# motor_frontplane.net
KiCad netlist of a schematic drawn in EAGLE
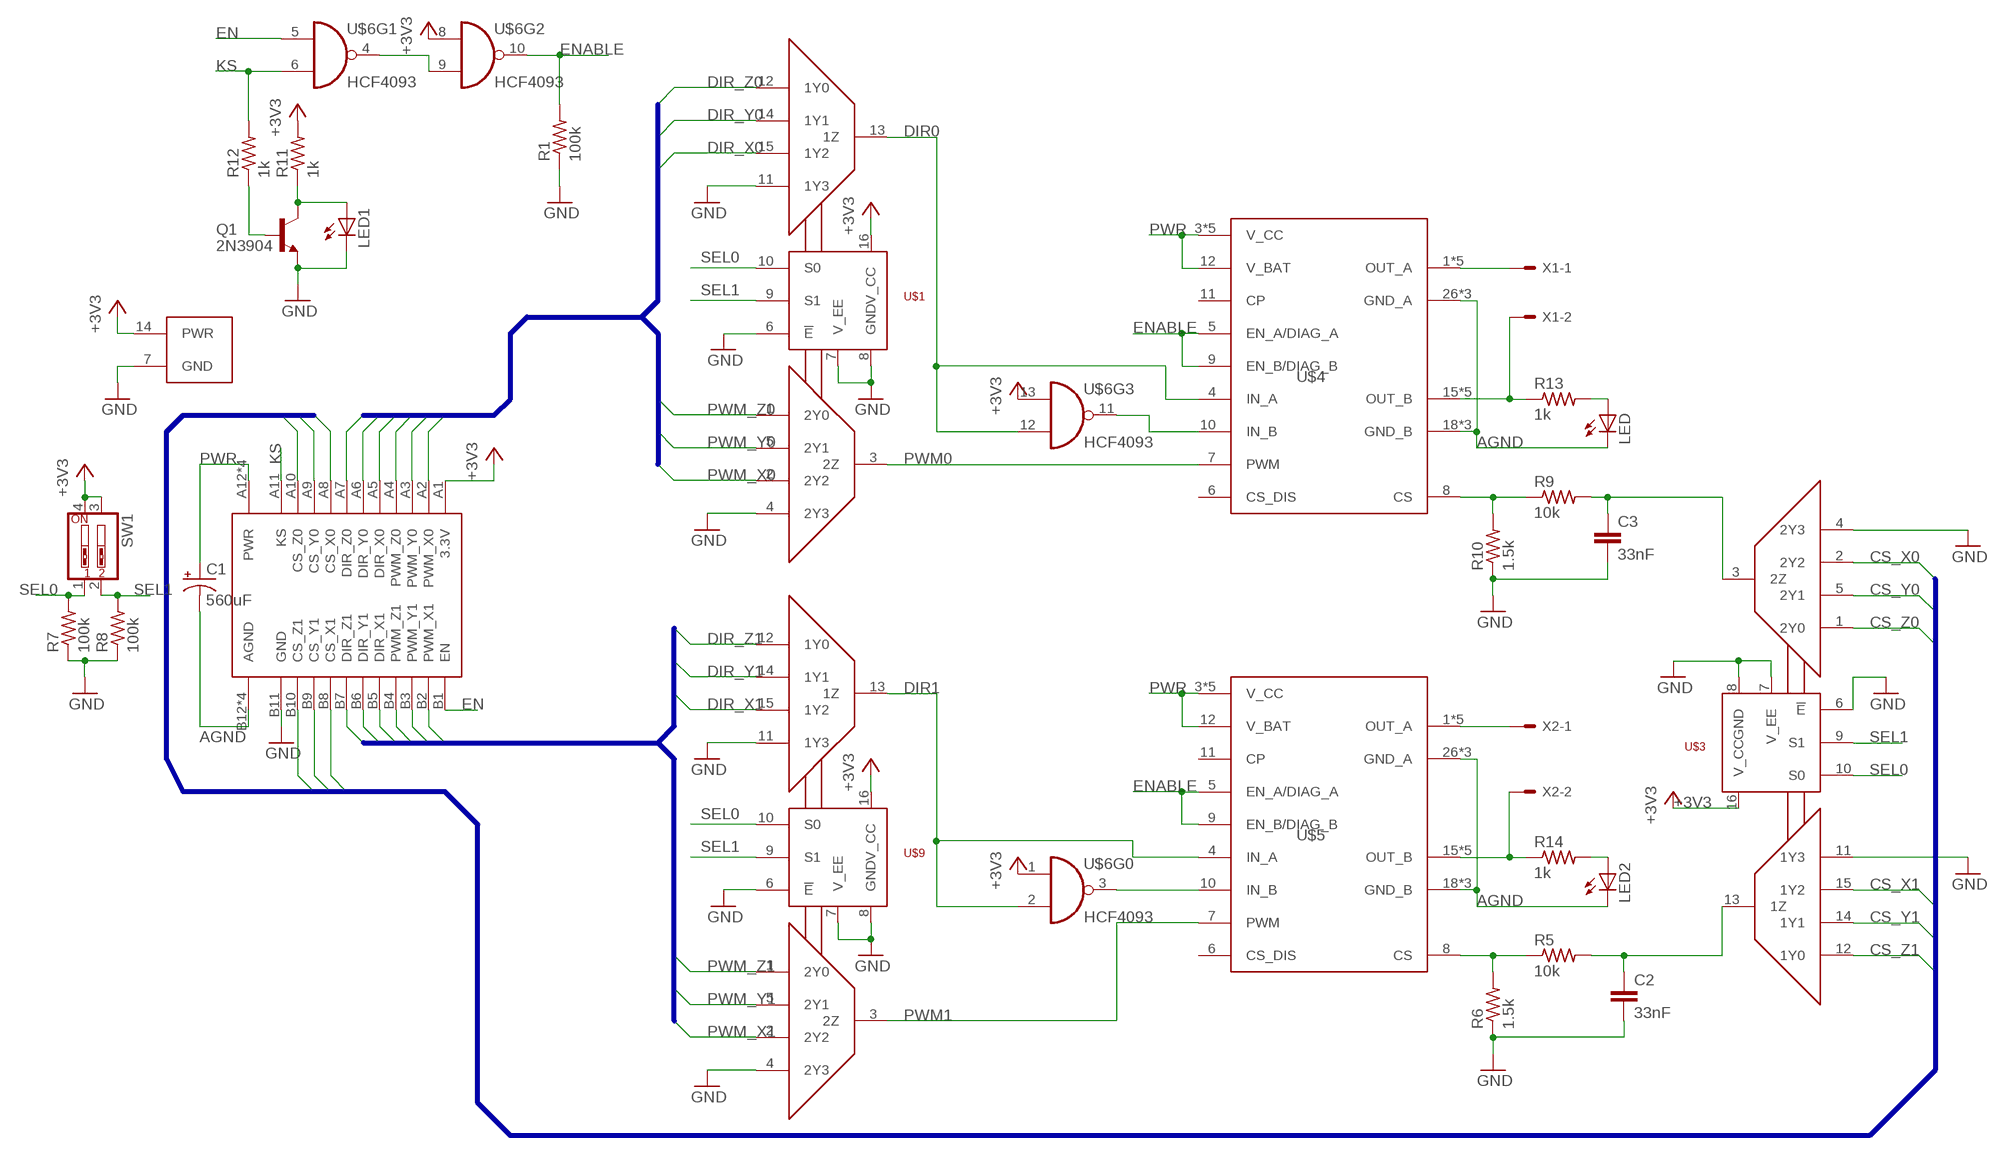
[diagram p0: schematic, sheet 1]

(export (version "E")
  (design (tool "Eeschema 10.0.6"))
  (components
    (comp (ref "C1")
      (value "560uF")
      (footprint "eagle-import:E3,5-10")
      (libsource (lib "eagle-import") (part "CPOL-USE3.5-10"))
    )
    (comp (ref "C2")
      (value "33nF")
      (footprint "eagle-import:C2.5-2")
      (libsource (lib "eagle-import") (part "C2.5/2"))
    )
    (comp (ref "C3")
      (value "33nF")
      (footprint "eagle-import:C2.5-2")
      (libsource (lib "eagle-import") (part "C2.5/2"))
    )
    (comp (ref "LED")
      (value "LED5MM")
      (footprint "eagle-import:LED5MM")
      (libsource (lib "eagle-import") (part "LED5MM"))
    )
    (comp (ref "LED1")
      (value "LED5MM")
      (footprint "eagle-import:LED5MM")
      (libsource (lib "eagle-import") (part "LED5MM"))
    )
    (comp (ref "LED2")
      (value "LED5MM")
      (footprint "eagle-import:LED5MM")
      (libsource (lib "eagle-import") (part "LED5MM"))
    )
    (comp (ref "Q1")
      (value "2N3904")
      (footprint "eagle-import:TO92")
      (libsource (lib "eagle-import") (part "2N3904"))
    )
    (comp (ref "R1")
      (value "100k")
      (footprint "eagle-import:R0805")
      (libsource (lib "eagle-import") (part "R-US_R0805"))
    )
    (comp (ref "R5")
      (value "10k")
      (footprint "eagle-import:R0805")
      (libsource (lib "eagle-import") (part "R-US_R0805"))
    )
    (comp (ref "R6")
      (value "1.5k")
      (footprint "eagle-import:R0805")
      (libsource (lib "eagle-import") (part "R-US_R0805"))
    )
    (comp (ref "R7")
      (value "100k")
      (footprint "eagle-import:R0805")
      (libsource (lib "eagle-import") (part "R-US_R0805"))
    )
    (comp (ref "R8")
      (value "100k")
      (footprint "eagle-import:R0805")
      (libsource (lib "eagle-import") (part "R-US_R0805"))
    )
    (comp (ref "R9")
      (value "10k")
      (footprint "eagle-import:R0805")
      (libsource (lib "eagle-import") (part "R-US_R0805"))
    )
    (comp (ref "R10")
      (value "1.5k")
      (footprint "eagle-import:R0805")
      (libsource (lib "eagle-import") (part "R-US_R0805"))
    )
    (comp (ref "R11")
      (value "1k")
      (footprint "eagle-import:R0805")
      (libsource (lib "eagle-import") (part "R-US_R0805"))
    )
    (comp (ref "R12")
      (value "1k")
      (footprint "eagle-import:R0805")
      (libsource (lib "eagle-import") (part "R-US_R0805"))
    )
    (comp (ref "R13")
      (value "1k")
      (footprint "eagle-import:R0805")
      (libsource (lib "eagle-import") (part "R-US_R0805"))
    )
    (comp (ref "R14")
      (value "1k")
      (footprint "eagle-import:R0805")
      (libsource (lib "eagle-import") (part "R-US_R0805"))
    )
    (comp (ref "SW1")
      (value "SW_DIP-2")
      (footprint "eagle-import:EDG-02")
      (libsource (lib "eagle-import") (part "SW_DIP-2"))
    )
    (comp (ref "U$1")
      (value "74HC4052-Q100")
      (footprint "eagle-import:SO16")
      (libsource (lib "eagle-import") (part "74HC4052-Q100"))
    )
    (comp (ref "U$2")
      (value "MOTOR_BOARD_CONN")
      (footprint "eagle-import:CARD_30PIN_8PWR")
      (libsource (lib "eagle-import") (part "MOTOR_BOARD_CONN"))
    )
    (comp (ref "U$3")
      (value "74HC4052-Q100")
      (footprint "eagle-import:SO16")
      (libsource (lib "eagle-import") (part "74HC4052-Q100"))
    )
    (comp (ref "U$4")
      (value "VNH5019A-E")
      (footprint "eagle-import:MULTIPOWERSO-30")
      (libsource (lib "eagle-import") (part "VNH5019A-E"))
    )
    (comp (ref "U$5")
      (value "VNH5019A-E")
      (footprint "eagle-import:MULTIPOWERSO-30")
      (libsource (lib "eagle-import") (part "VNH5019A-E"))
    )
    (comp (ref "U$6")
      (value "HCF4093")
      (footprint "eagle-import:SO14")
      (libsource (lib "eagle-import") (part "HCF4093"))
    )
    (comp (ref "U$9")
      (value "74HC4052-Q100")
      (footprint "eagle-import:SO16")
      (libsource (lib "eagle-import") (part "74HC4052-Q100"))
    )
    (comp (ref "X1")
      (value "KK-156-2")
      (footprint "eagle-import:KK-156-2")
      (libsource (lib "eagle-import") (part "KK-156-2"))
    )
    (comp (ref "X2")
      (value "KK-156-2")
      (footprint "eagle-import:KK-156-2")
      (libsource (lib "eagle-import") (part "KK-156-2"))
    )
  )
  (nets
    (net (code "1") (name "+3V3") (class "Default")
      (node (ref "R11") (pin "2") (pinfunction "2_2") (pintype "passive"))
      (node (ref "SW1") (pin "3") (pinfunction "3_3") (pintype "passive"))
      (node (ref "SW1") (pin "4") (pinfunction "4_4") (pintype "passive"))
      (node (ref "U$1") (pin "16") (pinfunction "V_CC_16") (pintype "bidirectional"))
      (node (ref "U$2") (pin "A1") (pinfunction "3.3V_A1") (pintype "bidirectional"))
      (node (ref "U$3") (pin "16") (pinfunction "V_CC_16") (pintype "bidirectional"))
      (node (ref "U$6") (pin "1") (pinfunction "I0_1") (pintype "input"))
      (node (ref "U$6") (pin "13") (pinfunction "I0_13") (pintype "input"))
      (node (ref "U$6") (pin "14") (pinfunction "PWR_14") (pintype "bidirectional"))
      (node (ref "U$6") (pin "8") (pinfunction "I0_8") (pintype "input"))
      (node (ref "U$9") (pin "16") (pinfunction "V_CC_16") (pintype "bidirectional"))
    )
    (net (code "2") (name "/AGND") (class "Default")
      (node (ref "C1") (pin "-") (pinfunction "-_-") (pintype "passive"))
      (node (ref "LED") (pin "K") (pinfunction "C_K") (pintype "passive"))
      (node (ref "LED2") (pin "K") (pinfunction "C_K") (pintype "passive"))
      (node (ref "U$2") (pin "B12") (pinfunction "AGND_B12") (pintype "bidirectional"))
      (node (ref "U$2") (pin "B13") (pinfunction "AGND_B13") (pintype "bidirectional"))
      (node (ref "U$2") (pin "B14") (pinfunction "AGND_B14") (pintype "bidirectional"))
      (node (ref "U$2") (pin "B15") (pinfunction "AGND_B15") (pintype "bidirectional"))
      (node (ref "U$4") (pin "18") (pinfunction "GND_B_18") (pintype "bidirectional"))
      (node (ref "U$4") (pin "19") (pinfunction "GND_B_19") (pintype "bidirectional"))
      (node (ref "U$4") (pin "20") (pinfunction "GND_B_20") (pintype "bidirectional"))
      (node (ref "U$4") (pin "26") (pinfunction "GND_A_26") (pintype "bidirectional"))
      (node (ref "U$4") (pin "27") (pinfunction "GND_A_27") (pintype "bidirectional"))
      (node (ref "U$4") (pin "28") (pinfunction "GND_A_28") (pintype "bidirectional"))
      (node (ref "U$5") (pin "18") (pinfunction "GND_B_18") (pintype "bidirectional"))
      (node (ref "U$5") (pin "19") (pinfunction "GND_B_19") (pintype "bidirectional"))
      (node (ref "U$5") (pin "20") (pinfunction "GND_B_20") (pintype "bidirectional"))
      (node (ref "U$5") (pin "26") (pinfunction "GND_A_26") (pintype "bidirectional"))
      (node (ref "U$5") (pin "27") (pinfunction "GND_A_27") (pintype "bidirectional"))
      (node (ref "U$5") (pin "28") (pinfunction "GND_A_28") (pintype "bidirectional"))
    )
    (net (code "3") (name "/CS_X0") (class "Default")
      (node (ref "U$2") (pin "A8") (pinfunction "CS_X0_A8") (pintype "bidirectional"))
      (node (ref "U$3") (pin "2") (pinfunction "2Y2_2") (pintype "bidirectional"))
    )
    (net (code "4") (name "/CS_X1") (class "Default")
      (node (ref "U$2") (pin "B8") (pinfunction "CS_X1_B8") (pintype "bidirectional"))
      (node (ref "U$3") (pin "15") (pinfunction "1Y2_15") (pintype "bidirectional"))
    )
    (net (code "5") (name "/CS_Y0") (class "Default")
      (node (ref "U$2") (pin "A9") (pinfunction "CS_Y0_A9") (pintype "bidirectional"))
      (node (ref "U$3") (pin "5") (pinfunction "2Y1_5") (pintype "bidirectional"))
    )
    (net (code "6") (name "/CS_Y1") (class "Default")
      (node (ref "U$2") (pin "B9") (pinfunction "CS_Y1_B9") (pintype "bidirectional"))
      (node (ref "U$3") (pin "14") (pinfunction "1Y1_14") (pintype "bidirectional"))
    )
    (net (code "7") (name "/CS_Z0") (class "Default")
      (node (ref "U$2") (pin "A10") (pinfunction "CS_Z0_A10") (pintype "bidirectional"))
      (node (ref "U$3") (pin "1") (pinfunction "2Y0_1") (pintype "bidirectional"))
    )
    (net (code "8") (name "/CS_Z1") (class "Default")
      (node (ref "U$2") (pin "B10") (pinfunction "CS_Z1_B10") (pintype "bidirectional"))
      (node (ref "U$3") (pin "12") (pinfunction "1Y0_12") (pintype "bidirectional"))
    )
    (net (code "9") (name "/DIR0") (class "Default")
      (node (ref "U$1") (pin "13") (pinfunction "1Z_13") (pintype "bidirectional"))
      (node (ref "U$4") (pin "4") (pinfunction "IN_A_4") (pintype "bidirectional"))
      (node (ref "U$6") (pin "12") (pinfunction "I1_12") (pintype "input"))
    )
    (net (code "10") (name "/DIR1") (class "Default")
      (node (ref "U$5") (pin "4") (pinfunction "IN_A_4") (pintype "bidirectional"))
      (node (ref "U$6") (pin "2") (pinfunction "I1_2") (pintype "input"))
      (node (ref "U$9") (pin "13") (pinfunction "1Z_13") (pintype "bidirectional"))
    )
    (net (code "11") (name "/DIR_X0") (class "Default")
      (node (ref "U$1") (pin "15") (pinfunction "1Y2_15") (pintype "bidirectional"))
      (node (ref "U$2") (pin "A5") (pinfunction "DIR_X0_A5") (pintype "bidirectional"))
    )
    (net (code "12") (name "/DIR_X1") (class "Default")
      (node (ref "U$2") (pin "B5") (pinfunction "DIR_X1_B5") (pintype "bidirectional"))
      (node (ref "U$9") (pin "15") (pinfunction "1Y2_15") (pintype "bidirectional"))
    )
    (net (code "13") (name "/DIR_Y0") (class "Default")
      (node (ref "U$1") (pin "14") (pinfunction "1Y1_14") (pintype "bidirectional"))
      (node (ref "U$2") (pin "A6") (pinfunction "DIR_Y0_A6") (pintype "bidirectional"))
    )
    (net (code "14") (name "/DIR_Y1") (class "Default")
      (node (ref "U$2") (pin "B6") (pinfunction "DIR_Y1_B6") (pintype "bidirectional"))
      (node (ref "U$9") (pin "14") (pinfunction "1Y1_14") (pintype "bidirectional"))
    )
    (net (code "15") (name "/DIR_Z0") (class "Default")
      (node (ref "U$1") (pin "12") (pinfunction "1Y0_12") (pintype "bidirectional"))
      (node (ref "U$2") (pin "A7") (pinfunction "DIR_Z0_A7") (pintype "bidirectional"))
    )
    (net (code "16") (name "/DIR_Z1") (class "Default")
      (node (ref "U$2") (pin "B7") (pinfunction "DIR_Z1_B7") (pintype "bidirectional"))
      (node (ref "U$9") (pin "12") (pinfunction "1Y0_12") (pintype "bidirectional"))
    )
    (net (code "17") (name "/EN") (class "Default")
      (node (ref "U$2") (pin "B1") (pinfunction "EN_B1") (pintype "bidirectional"))
      (node (ref "U$6") (pin "5") (pinfunction "I0_5") (pintype "input"))
    )
    (net (code "18") (name "/ENABLE") (class "Default")
      (node (ref "R1") (pin "2") (pinfunction "2_2") (pintype "passive"))
      (node (ref "U$4") (pin "5") (pinfunction "EN_A/DIAG_A_5") (pintype "bidirectional"))
      (node (ref "U$4") (pin "9") (pinfunction "EN_B/DIAG_B_9") (pintype "bidirectional"))
      (node (ref "U$5") (pin "5") (pinfunction "EN_A/DIAG_A_5") (pintype "bidirectional"))
      (node (ref "U$5") (pin "9") (pinfunction "EN_B/DIAG_B_9") (pintype "bidirectional"))
      (node (ref "U$6") (pin "10") (pinfunction "O_10") (pintype "output"))
    )
    (net (code "19") (name "/KS") (class "Default")
      (node (ref "R12") (pin "2") (pinfunction "2_2") (pintype "passive"))
      (node (ref "U$2") (pin "A11") (pinfunction "KS_A11") (pintype "bidirectional"))
      (node (ref "U$6") (pin "6") (pinfunction "I1_6") (pintype "input"))
    )
    (net (code "20") (name "/PWM0") (class "Default")
      (node (ref "U$1") (pin "3") (pinfunction "2Z_3") (pintype "bidirectional"))
      (node (ref "U$4") (pin "7") (pinfunction "PWM_7") (pintype "bidirectional"))
    )
    (net (code "21") (name "/PWM1") (class "Default")
      (node (ref "U$5") (pin "7") (pinfunction "PWM_7") (pintype "bidirectional"))
      (node (ref "U$9") (pin "3") (pinfunction "2Z_3") (pintype "bidirectional"))
    )
    (net (code "22") (name "/PWM_X0") (class "Default")
      (node (ref "U$1") (pin "2") (pinfunction "2Y2_2") (pintype "bidirectional"))
      (node (ref "U$2") (pin "A2") (pinfunction "PWM_X0_A2") (pintype "bidirectional"))
    )
    (net (code "23") (name "/PWM_X1") (class "Default")
      (node (ref "U$2") (pin "B2") (pinfunction "PWM_X1_B2") (pintype "bidirectional"))
      (node (ref "U$9") (pin "2") (pinfunction "2Y2_2") (pintype "bidirectional"))
    )
    (net (code "24") (name "/PWM_Y0") (class "Default")
      (node (ref "U$1") (pin "5") (pinfunction "2Y1_5") (pintype "bidirectional"))
      (node (ref "U$2") (pin "A3") (pinfunction "PWM_Y0_A3") (pintype "bidirectional"))
    )
    (net (code "25") (name "/PWM_Y1") (class "Default")
      (node (ref "U$2") (pin "B3") (pinfunction "PWM_Y1_B3") (pintype "bidirectional"))
      (node (ref "U$9") (pin "5") (pinfunction "2Y1_5") (pintype "bidirectional"))
    )
    (net (code "26") (name "/PWM_Z0") (class "Default")
      (node (ref "U$1") (pin "1") (pinfunction "2Y0_1") (pintype "bidirectional"))
      (node (ref "U$2") (pin "A4") (pinfunction "PWM_Z0_A4") (pintype "bidirectional"))
    )
    (net (code "27") (name "/PWM_Z1") (class "Default")
      (node (ref "U$2") (pin "B4") (pinfunction "PWM_Z1_B4") (pintype "bidirectional"))
      (node (ref "U$9") (pin "1") (pinfunction "2Y0_1") (pintype "bidirectional"))
    )
    (net (code "28") (name "/PWR") (class "Default")
      (node (ref "C1") (pin "+") (pinfunction "+_+") (pintype "passive"))
      (node (ref "U$2") (pin "A12") (pinfunction "PWR_A12") (pintype "bidirectional"))
      (node (ref "U$2") (pin "A13") (pinfunction "PWR_A13") (pintype "bidirectional"))
      (node (ref "U$2") (pin "A14") (pinfunction "PWR_A14") (pintype "bidirectional"))
      (node (ref "U$2") (pin "A15") (pinfunction "PWR_A15") (pintype "bidirectional"))
      (node (ref "U$4") (pin "12") (pinfunction "V_BAT_12") (pintype "bidirectional"))
      (node (ref "U$4") (pin "13") (pinfunction "V_CC_13") (pintype "bidirectional"))
      (node (ref "U$4") (pin "23") (pinfunction "V_CC_23") (pintype "bidirectional"))
      (node (ref "U$4") (pin "3") (pinfunction "V_CC_3") (pintype "bidirectional"))
      (node (ref "U$4") (pin "VCC") (pinfunction "V_CC_VCC") (pintype "bidirectional"))
      (node (ref "U$4") (pin "VCC@1") (pinfunction "V_CC_VCC@1") (pintype "bidirectional"))
      (node (ref "U$5") (pin "12") (pinfunction "V_BAT_12") (pintype "bidirectional"))
      (node (ref "U$5") (pin "13") (pinfunction "V_CC_13") (pintype "bidirectional"))
      (node (ref "U$5") (pin "23") (pinfunction "V_CC_23") (pintype "bidirectional"))
      (node (ref "U$5") (pin "3") (pinfunction "V_CC_3") (pintype "bidirectional"))
      (node (ref "U$5") (pin "VCC") (pinfunction "V_CC_VCC") (pintype "bidirectional"))
      (node (ref "U$5") (pin "VCC@1") (pinfunction "V_CC_VCC@1") (pintype "bidirectional"))
    )
    (net (code "29") (name "/SEL0") (class "Default")
      (node (ref "R7") (pin "2") (pinfunction "2_2") (pintype "passive"))
      (node (ref "SW1") (pin "1") (pinfunction "1_1") (pintype "passive"))
      (node (ref "U$1") (pin "10") (pinfunction "S0_10") (pintype "bidirectional"))
      (node (ref "U$3") (pin "10") (pinfunction "S0_10") (pintype "bidirectional"))
      (node (ref "U$9") (pin "10") (pinfunction "S0_10") (pintype "bidirectional"))
    )
    (net (code "30") (name "/SEL1") (class "Default")
      (node (ref "R8") (pin "2") (pinfunction "2_2") (pintype "passive"))
      (node (ref "SW1") (pin "2") (pinfunction "2_2") (pintype "passive"))
      (node (ref "U$1") (pin "9") (pinfunction "S1_9") (pintype "bidirectional"))
      (node (ref "U$3") (pin "9") (pinfunction "S1_9") (pintype "bidirectional"))
      (node (ref "U$9") (pin "9") (pinfunction "S1_9") (pintype "bidirectional"))
    )
    (net (code "31") (name "GND") (class "Default")
      (node (ref "C2") (pin "2") (pinfunction "2_2") (pintype "passive"))
      (node (ref "C3") (pin "2") (pinfunction "2_2") (pintype "passive"))
      (node (ref "LED1") (pin "K") (pinfunction "C_K") (pintype "passive"))
      (node (ref "Q1") (pin "3") (pinfunction "E_3") (pintype "passive"))
      (node (ref "R1") (pin "1") (pinfunction "1_1") (pintype "passive"))
      (node (ref "R10") (pin "1") (pinfunction "1_1") (pintype "passive"))
      (node (ref "R6") (pin "1") (pinfunction "1_1") (pintype "passive"))
      (node (ref "R7") (pin "1") (pinfunction "1_1") (pintype "passive"))
      (node (ref "R8") (pin "1") (pinfunction "1_1") (pintype "passive"))
      (node (ref "U$1") (pin "11") (pinfunction "1Y3_11") (pintype "bidirectional"))
      (node (ref "U$1") (pin "4") (pinfunction "2Y3_4") (pintype "bidirectional"))
      (node (ref "U$1") (pin "6") (pinfunction "~{E}_6") (pintype "bidirectional"))
      (node (ref "U$1") (pin "7") (pinfunction "V_EE_7") (pintype "bidirectional"))
      (node (ref "U$1") (pin "8") (pinfunction "GND_8") (pintype "bidirectional"))
      (node (ref "U$2") (pin "B11") (pinfunction "GND_B11") (pintype "bidirectional"))
      (node (ref "U$3") (pin "11") (pinfunction "1Y3_11") (pintype "bidirectional"))
      (node (ref "U$3") (pin "4") (pinfunction "2Y3_4") (pintype "bidirectional"))
      (node (ref "U$3") (pin "6") (pinfunction "~{E}_6") (pintype "bidirectional"))
      (node (ref "U$3") (pin "7") (pinfunction "V_EE_7") (pintype "bidirectional"))
      (node (ref "U$3") (pin "8") (pinfunction "GND_8") (pintype "bidirectional"))
      (node (ref "U$6") (pin "7") (pinfunction "GND_7") (pintype "bidirectional"))
      (node (ref "U$9") (pin "11") (pinfunction "1Y3_11") (pintype "bidirectional"))
      (node (ref "U$9") (pin "4") (pinfunction "2Y3_4") (pintype "bidirectional"))
      (node (ref "U$9") (pin "6") (pinfunction "~{E}_6") (pintype "bidirectional"))
      (node (ref "U$9") (pin "7") (pinfunction "V_EE_7") (pintype "bidirectional"))
      (node (ref "U$9") (pin "8") (pinfunction "GND_8") (pintype "bidirectional"))
    )
    (net (code "32") (name "Net-(LED-PadA)") (class "Default")
      (node (ref "LED") (pin "A") (pinfunction "A_A") (pintype "passive"))
      (node (ref "R13") (pin "2") (pinfunction "2_2") (pintype "passive"))
    )
    (net (code "33") (name "Net-(LED2-PadA)") (class "Default")
      (node (ref "LED2") (pin "A") (pinfunction "A_A") (pintype "passive"))
      (node (ref "R14") (pin "2") (pinfunction "2_2") (pintype "passive"))
    )
    (net (code "34") (name "Net-(Q1-B)") (class "Default")
      (node (ref "Q1") (pin "2") (pinfunction "B_2") (pintype "passive"))
      (node (ref "R12") (pin "1") (pinfunction "1_1") (pintype "passive"))
    )
    (net (code "35") (name "Net-(Q1-C)") (class "Default")
      (node (ref "LED1") (pin "A") (pinfunction "A_A") (pintype "passive"))
      (node (ref "Q1") (pin "1") (pinfunction "C_1") (pintype "passive"))
      (node (ref "R11") (pin "1") (pinfunction "1_1") (pintype "passive"))
    )
    (net (code "36") (name "Net-(U$3-1Z)") (class "Default")
      (node (ref "C2") (pin "1") (pinfunction "1_1") (pintype "passive"))
      (node (ref "R5") (pin "2") (pinfunction "2_2") (pintype "passive"))
      (node (ref "U$3") (pin "13") (pinfunction "1Z_13") (pintype "bidirectional"))
    )
    (net (code "37") (name "Net-(U$3-2Z)") (class "Default")
      (node (ref "C3") (pin "1") (pinfunction "1_1") (pintype "passive"))
      (node (ref "R9") (pin "2") (pinfunction "2_2") (pintype "passive"))
      (node (ref "U$3") (pin "3") (pinfunction "2Z_3") (pintype "bidirectional"))
    )
    (net (code "38") (name "Net-(U$4-CS)") (class "Default")
      (node (ref "R10") (pin "2") (pinfunction "2_2") (pintype "passive"))
      (node (ref "R9") (pin "1") (pinfunction "1_1") (pintype "passive"))
      (node (ref "U$4") (pin "8") (pinfunction "CS_8") (pintype "bidirectional"))
    )
    (net (code "39") (name "Net-(U$4-IN_B)") (class "Default")
      (node (ref "U$4") (pin "10") (pinfunction "IN_B_10") (pintype "bidirectional"))
      (node (ref "U$6") (pin "11") (pinfunction "O_11") (pintype "output"))
    )
    (net (code "40") (name "Net-(U$5-CS)") (class "Default")
      (node (ref "R5") (pin "1") (pinfunction "1_1") (pintype "passive"))
      (node (ref "R6") (pin "2") (pinfunction "2_2") (pintype "passive"))
      (node (ref "U$5") (pin "8") (pinfunction "CS_8") (pintype "bidirectional"))
    )
    (net (code "41") (name "Net-(U$5-IN_B)") (class "Default")
      (node (ref "U$5") (pin "10") (pinfunction "IN_B_10") (pintype "bidirectional"))
      (node (ref "U$6") (pin "3") (pinfunction "O_3") (pintype "output"))
    )
    (net (code "42") (name "Net-(U$6C-O)") (class "Default")
      (node (ref "U$6") (pin "4") (pinfunction "O_4") (pintype "output"))
      (node (ref "U$6") (pin "9") (pinfunction "I1_9") (pintype "input"))
    )
    (net (code "43") (name "Net-(X1A-S)") (class "Default")
      (node (ref "U$4") (pin "1") (pinfunction "OUT_A_1") (pintype "bidirectional"))
      (node (ref "U$4") (pin "25") (pinfunction "OUT_A_25") (pintype "bidirectional"))
      (node (ref "U$4") (pin "30") (pinfunction "OUT_A_30") (pintype "bidirectional"))
      (node (ref "U$4") (pin "OUTA") (pinfunction "OUT_A_OUTA") (pintype "bidirectional"))
      (node (ref "U$4") (pin "OUTA@1") (pinfunction "OUT_A_OUTA@1") (pintype "bidirectional"))
      (node (ref "X1") (pin "1") (pinfunction "S_1") (pintype "passive"))
    )
    (net (code "44") (name "Net-(X1B-S)") (class "Default")
      (node (ref "R13") (pin "1") (pinfunction "1_1") (pintype "passive"))
      (node (ref "U$4") (pin "15") (pinfunction "OUT_B_15") (pintype "bidirectional"))
      (node (ref "U$4") (pin "16") (pinfunction "OUT_B_16") (pintype "bidirectional"))
      (node (ref "U$4") (pin "21") (pinfunction "OUT_B_21") (pintype "bidirectional"))
      (node (ref "U$4") (pin "OUTB") (pinfunction "OUT_B_OUTB") (pintype "bidirectional"))
      (node (ref "U$4") (pin "OUTB@1") (pinfunction "OUT_B_OUTB@1") (pintype "bidirectional"))
      (node (ref "X1") (pin "2") (pinfunction "S_2") (pintype "passive"))
    )
    (net (code "45") (name "Net-(X2A-S)") (class "Default")
      (node (ref "U$5") (pin "1") (pinfunction "OUT_A_1") (pintype "bidirectional"))
      (node (ref "U$5") (pin "25") (pinfunction "OUT_A_25") (pintype "bidirectional"))
      (node (ref "U$5") (pin "30") (pinfunction "OUT_A_30") (pintype "bidirectional"))
      (node (ref "U$5") (pin "OUTA") (pinfunction "OUT_A_OUTA") (pintype "bidirectional"))
      (node (ref "U$5") (pin "OUTA@1") (pinfunction "OUT_A_OUTA@1") (pintype "bidirectional"))
      (node (ref "X2") (pin "1") (pinfunction "S_1") (pintype "passive"))
    )
    (net (code "46") (name "Net-(X2B-S)") (class "Default")
      (node (ref "R14") (pin "1") (pinfunction "1_1") (pintype "passive"))
      (node (ref "U$5") (pin "15") (pinfunction "OUT_B_15") (pintype "bidirectional"))
      (node (ref "U$5") (pin "16") (pinfunction "OUT_B_16") (pintype "bidirectional"))
      (node (ref "U$5") (pin "21") (pinfunction "OUT_B_21") (pintype "bidirectional"))
      (node (ref "U$5") (pin "OUTB") (pinfunction "OUT_B_OUTB") (pintype "bidirectional"))
      (node (ref "U$5") (pin "OUTB@1") (pinfunction "OUT_B_OUTB@1") (pintype "bidirectional"))
      (node (ref "X2") (pin "2") (pinfunction "S_2") (pintype "passive"))
    )
    (net (code "47") (name "unconnected-(U$4-CP-Pad11)") (class "Default")
      (node (ref "U$4") (pin "11") (pinfunction "CP_11") (pintype "bidirectional"))
    )
    (net (code "48") (name "unconnected-(U$4-CS_DIS-Pad6)") (class "Default")
      (node (ref "U$4") (pin "6") (pinfunction "CS_DIS_6") (pintype "bidirectional"))
    )
    (net (code "49") (name "unconnected-(U$5-CP-Pad11)") (class "Default")
      (node (ref "U$5") (pin "11") (pinfunction "CP_11") (pintype "bidirectional"))
    )
    (net (code "50") (name "unconnected-(U$5-CS_DIS-Pad6)") (class "Default")
      (node (ref "U$5") (pin "6") (pinfunction "CS_DIS_6") (pintype "bidirectional"))
    )
  )
)
